# HW4.net
KiCad netlist of a schematic drawn in EAGLE
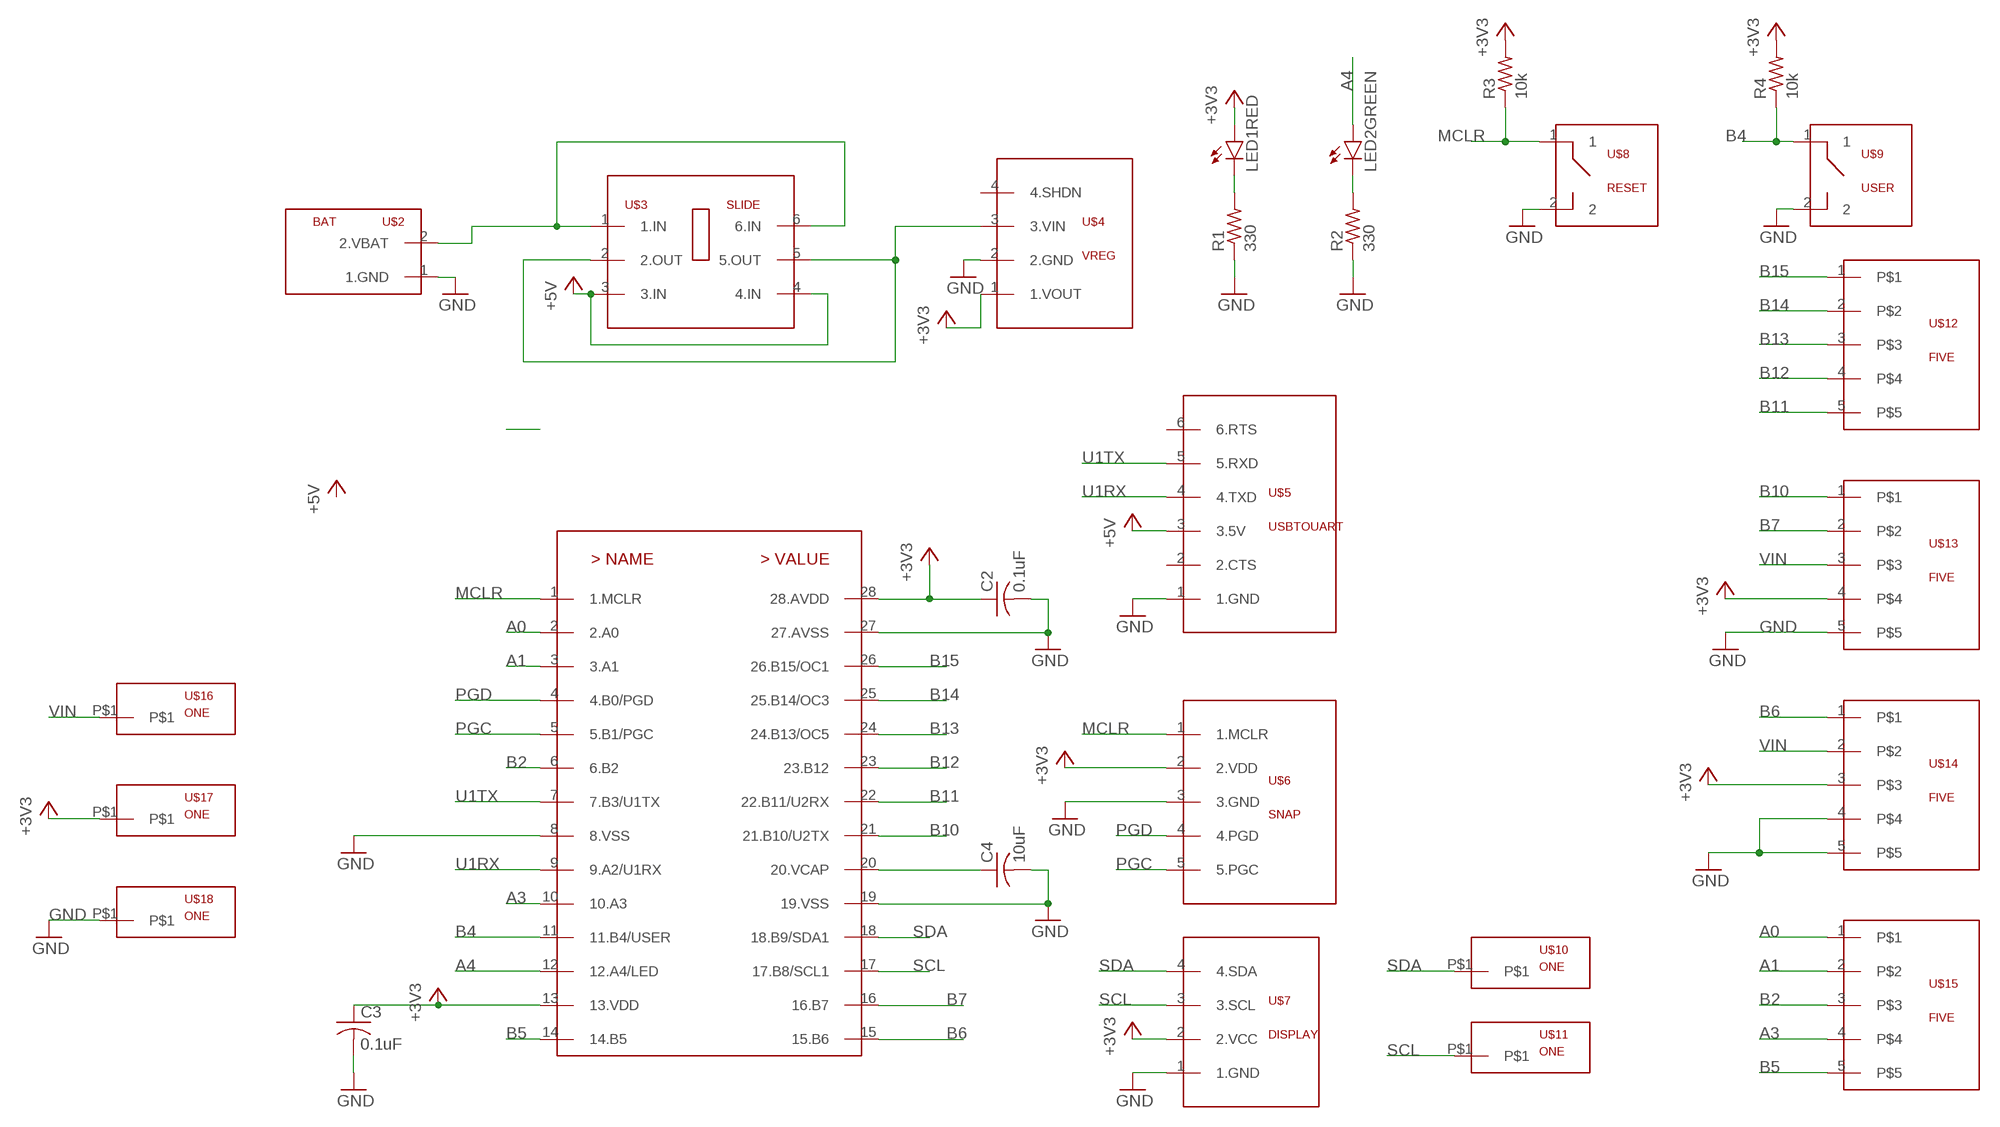
[diagram p0: schematic, sheet 1]

(export (version "E")
  (design (tool "Eeschema 10.0.6"))
  (components
    (comp (ref "C2")
      (value "0.1uF")
      (footprint "eagle-import:C025-024X044")
      (libsource (lib "eagle-import") (part "C-US025-024X044"))
    )
    (comp (ref "C3")
      (value "0.1uF")
      (footprint "eagle-import:C025-024X044")
      (libsource (lib "eagle-import") (part "C-US025-024X044"))
    )
    (comp (ref "C4")
      (value "10uF")
      (footprint "eagle-import:C025-024X044")
      (libsource (lib "eagle-import") (part "C-US025-024X044"))
    )
    (comp (ref "LED1RED")
      (value "LED3MM")
      (footprint "eagle-import:LED3MM")
      (libsource (lib "eagle-import") (part "LED3MM"))
    )
    (comp (ref "LED2GREEN")
      (value "LED3MM")
      (footprint "eagle-import:LED3MM")
      (libsource (lib "eagle-import") (part "LED3MM"))
    )
    (comp (ref "R1")
      (value "330")
      (footprint "eagle-import:0207_7")
      (libsource (lib "eagle-import") (part "R-US_0207/7"))
    )
    (comp (ref "R2")
      (value "330")
      (footprint "eagle-import:0207_7")
      (libsource (lib "eagle-import") (part "R-US_0207/7"))
    )
    (comp (ref "R3")
      (value "10k")
      (footprint "eagle-import:0207_7")
      (libsource (lib "eagle-import") (part "R-US_0207/7"))
    )
    (comp (ref "R4")
      (value "10k")
      (footprint "eagle-import:0207_7")
      (libsource (lib "eagle-import") (part "R-US_0207/7"))
    )
    (comp (ref "U$1")
      (value "PIC32")
      (footprint "eagle-import:DIL28-3")
      (libsource (lib "eagle-import") (part "PIC32"))
    )
    (comp (ref "U$2")
      (value "BAT")
      (footprint "eagle-import:BAT")
      (libsource (lib "eagle-import") (part "BAT"))
    )
    (comp (ref "U$3")
      (value "SLIDE")
      (footprint "eagle-import:SLIDE")
      (libsource (lib "eagle-import") (part "SLIDE"))
    )
    (comp (ref "U$4")
      (value "VREG")
      (footprint "eagle-import:VREG")
      (libsource (lib "eagle-import") (part "VREG"))
    )
    (comp (ref "U$5")
      (value "USBTOUART")
      (footprint "eagle-import:USBTOUART")
      (libsource (lib "eagle-import") (part "USBTOUART"))
    )
    (comp (ref "U$6")
      (value "SNAP")
      (footprint "eagle-import:SNAP")
      (libsource (lib "eagle-import") (part "SNAP"))
    )
    (comp (ref "U$7")
      (value "DISPLAY")
      (footprint "eagle-import:DISPLAY")
      (libsource (lib "eagle-import") (part "DISPLAY"))
    )
    (comp (ref "U$8")
      (value "RESET")
      (footprint "eagle-import:BUTTON")
      (libsource (lib "eagle-import") (part "BUTTON"))
    )
    (comp (ref "U$9")
      (value "USER")
      (footprint "eagle-import:BUTTON")
      (libsource (lib "eagle-import") (part "BUTTON"))
    )
    (comp (ref "U$10")
      (value "ONE")
      (footprint "eagle-import:ONE")
      (libsource (lib "eagle-import") (part "ONE"))
    )
    (comp (ref "U$11")
      (value "ONE")
      (footprint "eagle-import:ONE")
      (libsource (lib "eagle-import") (part "ONE"))
    )
    (comp (ref "U$12")
      (value "FIVE")
      (footprint "eagle-import:FIVE")
      (libsource (lib "eagle-import") (part "FIVE"))
    )
    (comp (ref "U$13")
      (value "FIVE")
      (footprint "eagle-import:FIVE")
      (libsource (lib "eagle-import") (part "FIVE"))
    )
    (comp (ref "U$14")
      (value "FIVE")
      (footprint "eagle-import:FIVE")
      (libsource (lib "eagle-import") (part "FIVE"))
    )
    (comp (ref "U$15")
      (value "FIVE")
      (footprint "eagle-import:FIVE")
      (libsource (lib "eagle-import") (part "FIVE"))
    )
    (comp (ref "U$16")
      (value "ONE")
      (footprint "eagle-import:ONE")
      (libsource (lib "eagle-import") (part "ONE"))
    )
    (comp (ref "U$17")
      (value "ONE")
      (footprint "eagle-import:ONE")
      (libsource (lib "eagle-import") (part "ONE"))
    )
    (comp (ref "U$18")
      (value "ONE")
      (footprint "eagle-import:ONE")
      (libsource (lib "eagle-import") (part "ONE"))
    )
  )
  (nets
    (net (code "1") (name "+3V3") (class "Default")
      (node (ref "C2") (pin "1") (pinfunction "1_1") (pintype "passive"))
      (node (ref "C3") (pin "1") (pinfunction "1_1") (pintype "passive"))
      (node (ref "LED1RED") (pin "A") (pinfunction "A_A") (pintype "passive"))
      (node (ref "R3") (pin "2") (pinfunction "2_2") (pintype "passive"))
      (node (ref "R4") (pin "2") (pinfunction "2_2") (pintype "passive"))
      (node (ref "U$1") (pin "13") (pinfunction "13.VDD_13") (pintype "bidirectional"))
      (node (ref "U$1") (pin "28") (pinfunction "28.AVDD_28") (pintype "bidirectional"))
      (node (ref "U$13") (pin "4") (pinfunction "P$4_4") (pintype "bidirectional"))
      (node (ref "U$14") (pin "3") (pinfunction "P$3_3") (pintype "bidirectional"))
      (node (ref "U$17") (pin "P$1") (pinfunction "P$1_P$1") (pintype "bidirectional"))
      (node (ref "U$4") (pin "1") (pinfunction "1.VOUT_1") (pintype "bidirectional"))
      (node (ref "U$6") (pin "2") (pinfunction "2.VDD_2") (pintype "bidirectional"))
      (node (ref "U$7") (pin "2") (pinfunction "2.VCC_2") (pintype "bidirectional"))
    )
    (net (code "2") (name "+5V") (class "Default")
      (node (ref "U$3") (pin "3") (pinfunction "3.IN_3") (pintype "bidirectional"))
      (node (ref "U$3") (pin "4") (pinfunction "4.IN_4") (pintype "bidirectional"))
      (node (ref "U$5") (pin "3") (pinfunction "3.5V_3") (pintype "bidirectional"))
    )
    (net (code "3") (name "/A0") (class "Default")
      (node (ref "U$1") (pin "2") (pinfunction "2.A0_2") (pintype "bidirectional"))
      (node (ref "U$15") (pin "1") (pinfunction "P$1_1") (pintype "bidirectional"))
    )
    (net (code "4") (name "/A1") (class "Default")
      (node (ref "U$1") (pin "3") (pinfunction "3.A1_3") (pintype "bidirectional"))
      (node (ref "U$15") (pin "2") (pinfunction "P$2_2") (pintype "bidirectional"))
    )
    (net (code "5") (name "/A3") (class "Default")
      (node (ref "U$1") (pin "10") (pinfunction "10.A3_10") (pintype "bidirectional"))
      (node (ref "U$15") (pin "4") (pinfunction "P$4_4") (pintype "bidirectional"))
    )
    (net (code "6") (name "/A4") (class "Default")
      (node (ref "LED2GREEN") (pin "A") (pinfunction "A_A") (pintype "passive"))
      (node (ref "U$1") (pin "12") (pinfunction "12.A4/LED_12") (pintype "bidirectional"))
    )
    (net (code "7") (name "/B2") (class "Default")
      (node (ref "U$1") (pin "6") (pinfunction "6.B2_6") (pintype "bidirectional"))
      (node (ref "U$15") (pin "3") (pinfunction "P$3_3") (pintype "bidirectional"))
    )
    (net (code "8") (name "/B4") (class "Default")
      (node (ref "R4") (pin "1") (pinfunction "1_1") (pintype "passive"))
      (node (ref "U$1") (pin "11") (pinfunction "11.B4/USER_11") (pintype "bidirectional"))
      (node (ref "U$9") (pin "1") (pinfunction "1_1") (pintype "bidirectional"))
    )
    (net (code "9") (name "/B5") (class "Default")
      (node (ref "U$1") (pin "14") (pinfunction "14.B5_14") (pintype "bidirectional"))
      (node (ref "U$15") (pin "5") (pinfunction "P$5_5") (pintype "bidirectional"))
    )
    (net (code "10") (name "/B6") (class "Default")
      (node (ref "U$1") (pin "15") (pinfunction "15.B6_15") (pintype "bidirectional"))
      (node (ref "U$14") (pin "1") (pinfunction "P$1_1") (pintype "bidirectional"))
    )
    (net (code "11") (name "/B7") (class "Default")
      (node (ref "U$1") (pin "16") (pinfunction "16.B7_16") (pintype "bidirectional"))
      (node (ref "U$13") (pin "2") (pinfunction "P$2_2") (pintype "bidirectional"))
    )
    (net (code "12") (name "/B10") (class "Default")
      (node (ref "U$1") (pin "21") (pinfunction "21.B10/U2TX_21") (pintype "bidirectional"))
      (node (ref "U$13") (pin "1") (pinfunction "P$1_1") (pintype "bidirectional"))
    )
    (net (code "13") (name "/B11") (class "Default")
      (node (ref "U$1") (pin "22") (pinfunction "22.B11/U2RX_22") (pintype "bidirectional"))
      (node (ref "U$12") (pin "5") (pinfunction "P$5_5") (pintype "bidirectional"))
    )
    (net (code "14") (name "/B12") (class "Default")
      (node (ref "U$1") (pin "23") (pinfunction "23.B12_23") (pintype "bidirectional"))
      (node (ref "U$12") (pin "4") (pinfunction "P$4_4") (pintype "bidirectional"))
    )
    (net (code "15") (name "/B13") (class "Default")
      (node (ref "U$1") (pin "24") (pinfunction "24.B13/OC5_24") (pintype "bidirectional"))
      (node (ref "U$12") (pin "3") (pinfunction "P$3_3") (pintype "bidirectional"))
    )
    (net (code "16") (name "/B14") (class "Default")
      (node (ref "U$1") (pin "25") (pinfunction "25.B14/OC3_25") (pintype "bidirectional"))
      (node (ref "U$12") (pin "2") (pinfunction "P$2_2") (pintype "bidirectional"))
    )
    (net (code "17") (name "/B15") (class "Default")
      (node (ref "U$1") (pin "26") (pinfunction "26.B15/OC1_26") (pintype "bidirectional"))
      (node (ref "U$12") (pin "1") (pinfunction "P$1_1") (pintype "bidirectional"))
    )
    (net (code "18") (name "/MCLR") (class "Default")
      (node (ref "R3") (pin "1") (pinfunction "1_1") (pintype "passive"))
      (node (ref "U$1") (pin "1") (pinfunction "1.MCLR_1") (pintype "bidirectional"))
      (node (ref "U$6") (pin "1") (pinfunction "1.MCLR_1") (pintype "bidirectional"))
      (node (ref "U$8") (pin "1") (pinfunction "1_1") (pintype "bidirectional"))
    )
    (net (code "19") (name "/PGC") (class "Default")
      (node (ref "U$1") (pin "5") (pinfunction "5.B1/PGC_5") (pintype "bidirectional"))
      (node (ref "U$6") (pin "5") (pinfunction "5.PGC_5") (pintype "bidirectional"))
    )
    (net (code "20") (name "/PGD") (class "Default")
      (node (ref "U$1") (pin "4") (pinfunction "4.B0/PGD_4") (pintype "bidirectional"))
      (node (ref "U$6") (pin "4") (pinfunction "4.PGD_4") (pintype "bidirectional"))
    )
    (net (code "21") (name "/SCL") (class "Default")
      (node (ref "U$1") (pin "17") (pinfunction "17.B8/SCL1_17") (pintype "bidirectional"))
      (node (ref "U$11") (pin "P$1") (pinfunction "P$1_P$1") (pintype "bidirectional"))
      (node (ref "U$7") (pin "3") (pinfunction "3.SCL_3") (pintype "bidirectional"))
    )
    (net (code "22") (name "/SDA") (class "Default")
      (node (ref "U$1") (pin "18") (pinfunction "18.B9/SDA1_18") (pintype "bidirectional"))
      (node (ref "U$10") (pin "P$1") (pinfunction "P$1_P$1") (pintype "bidirectional"))
      (node (ref "U$7") (pin "4") (pinfunction "4.SDA_4") (pintype "bidirectional"))
    )
    (net (code "23") (name "/U1RX") (class "Default")
      (node (ref "U$1") (pin "9") (pinfunction "9.A2/U1RX_9") (pintype "bidirectional"))
      (node (ref "U$5") (pin "4") (pinfunction "4.TXD_4") (pintype "bidirectional"))
    )
    (net (code "24") (name "/U1TX") (class "Default")
      (node (ref "U$1") (pin "7") (pinfunction "7.B3/U1TX_7") (pintype "bidirectional"))
      (node (ref "U$5") (pin "5") (pinfunction "5.RXD_5") (pintype "bidirectional"))
    )
    (net (code "25") (name "/VIN") (class "Default")
      (node (ref "U$13") (pin "3") (pinfunction "P$3_3") (pintype "bidirectional"))
      (node (ref "U$14") (pin "2") (pinfunction "P$2_2") (pintype "bidirectional"))
      (node (ref "U$16") (pin "P$1") (pinfunction "P$1_P$1") (pintype "bidirectional"))
    )
    (net (code "26") (name "GND") (class "Default")
      (node (ref "C2") (pin "2") (pinfunction "2_2") (pintype "passive"))
      (node (ref "C3") (pin "2") (pinfunction "2_2") (pintype "passive"))
      (node (ref "C4") (pin "2") (pinfunction "2_2") (pintype "passive"))
      (node (ref "R1") (pin "1") (pinfunction "1_1") (pintype "passive"))
      (node (ref "R2") (pin "1") (pinfunction "1_1") (pintype "passive"))
      (node (ref "U$1") (pin "19") (pinfunction "19.VSS_19") (pintype "bidirectional"))
      (node (ref "U$1") (pin "27") (pinfunction "27.AVSS_27") (pintype "bidirectional"))
      (node (ref "U$1") (pin "8") (pinfunction "8.VSS_8") (pintype "bidirectional"))
      (node (ref "U$13") (pin "5") (pinfunction "P$5_5") (pintype "bidirectional"))
      (node (ref "U$14") (pin "4") (pinfunction "P$4_4") (pintype "bidirectional"))
      (node (ref "U$14") (pin "5") (pinfunction "P$5_5") (pintype "bidirectional"))
      (node (ref "U$18") (pin "P$1") (pinfunction "P$1_P$1") (pintype "bidirectional"))
      (node (ref "U$2") (pin "1") (pinfunction "1.GND_1") (pintype "bidirectional"))
      (node (ref "U$4") (pin "2") (pinfunction "2.GND_2") (pintype "bidirectional"))
      (node (ref "U$5") (pin "1") (pinfunction "1.GND_1") (pintype "bidirectional"))
      (node (ref "U$6") (pin "3") (pinfunction "3.GND_3") (pintype "bidirectional"))
      (node (ref "U$7") (pin "1") (pinfunction "1.GND_1") (pintype "bidirectional"))
      (node (ref "U$8") (pin "2") (pinfunction "2_2") (pintype "bidirectional"))
      (node (ref "U$9") (pin "2") (pinfunction "2_2") (pintype "bidirectional"))
    )
    (net (code "27") (name "Net-(LED1RED-C)") (class "Default")
      (node (ref "LED1RED") (pin "K") (pinfunction "C_K") (pintype "passive"))
      (node (ref "R1") (pin "2") (pinfunction "2_2") (pintype "passive"))
    )
    (net (code "28") (name "Net-(LED2GREEN-C)") (class "Default")
      (node (ref "LED2GREEN") (pin "K") (pinfunction "C_K") (pintype "passive"))
      (node (ref "R2") (pin "2") (pinfunction "2_2") (pintype "passive"))
    )
    (net (code "29") (name "Net-(U$1-20.VCAP)") (class "Default")
      (node (ref "C4") (pin "1") (pinfunction "1_1") (pintype "passive"))
      (node (ref "U$1") (pin "20") (pinfunction "20.VCAP_20") (pintype "bidirectional"))
    )
    (net (code "30") (name "Net-(U$2-2.VBAT)") (class "Default")
      (node (ref "U$2") (pin "2") (pinfunction "2.VBAT_2") (pintype "bidirectional"))
      (node (ref "U$3") (pin "1") (pinfunction "1.IN_1") (pintype "bidirectional"))
      (node (ref "U$3") (pin "6") (pinfunction "6.IN_6") (pintype "bidirectional"))
    )
    (net (code "31") (name "Net-(U$3-2.OUT)") (class "Default")
      (node (ref "U$3") (pin "2") (pinfunction "2.OUT_2") (pintype "bidirectional"))
      (node (ref "U$3") (pin "5") (pinfunction "5.OUT_5") (pintype "bidirectional"))
      (node (ref "U$4") (pin "3") (pinfunction "3.VIN_3") (pintype "bidirectional"))
    )
    (net (code "32") (name "unconnected-(U$4-4.SHDN-Pad4)") (class "Default")
      (node (ref "U$4") (pin "4") (pinfunction "4.SHDN_4") (pintype "bidirectional"))
    )
    (net (code "33") (name "unconnected-(U$5-2.CTS-Pad2)") (class "Default")
      (node (ref "U$5") (pin "2") (pinfunction "2.CTS_2") (pintype "bidirectional"))
    )
    (net (code "34") (name "unconnected-(U$5-6.RTS-Pad6)") (class "Default")
      (node (ref "U$5") (pin "6") (pinfunction "6.RTS_6") (pintype "bidirectional"))
    )
  )
)
